# dio_adapter.net
KiCad netlist of a schematic drawn in EAGLE
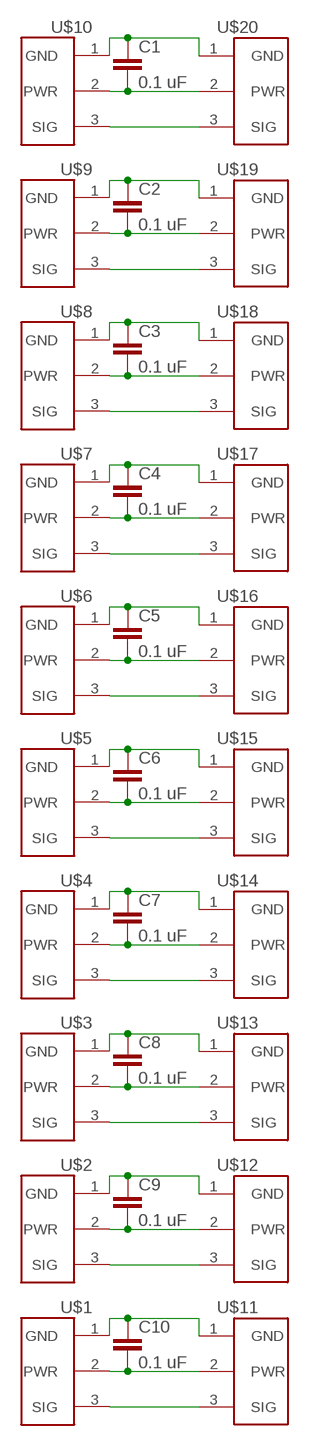
[diagram p0: schematic, sheet 1]

(export (version "E")
  (design (tool "Eeschema 10.0.6"))
  (components
    (comp (ref "C1")
      (value "0.1 uF")
      (footprint "eagle-import:0603")
      (libsource (lib "eagle-import") (part "CAP0603"))
    )
    (comp (ref "C2")
      (value "0.1 uF")
      (footprint "eagle-import:0603")
      (libsource (lib "eagle-import") (part "CAP0603"))
    )
    (comp (ref "C3")
      (value "0.1 uF")
      (footprint "eagle-import:0603")
      (libsource (lib "eagle-import") (part "CAP0603"))
    )
    (comp (ref "C4")
      (value "0.1 uF")
      (footprint "eagle-import:0603")
      (libsource (lib "eagle-import") (part "CAP0603"))
    )
    (comp (ref "C5")
      (value "0.1 uF")
      (footprint "eagle-import:0603")
      (libsource (lib "eagle-import") (part "CAP0603"))
    )
    (comp (ref "C6")
      (value "0.1 uF")
      (footprint "eagle-import:0603")
      (libsource (lib "eagle-import") (part "CAP0603"))
    )
    (comp (ref "C7")
      (value "0.1 uF")
      (footprint "eagle-import:0603")
      (libsource (lib "eagle-import") (part "CAP0603"))
    )
    (comp (ref "C8")
      (value "0.1 uF")
      (footprint "eagle-import:0603")
      (libsource (lib "eagle-import") (part "CAP0603"))
    )
    (comp (ref "C9")
      (value "0.1 uF")
      (footprint "eagle-import:0603")
      (libsource (lib "eagle-import") (part "CAP0603"))
    )
    (comp (ref "C10")
      (value "0.1 uF")
      (footprint "eagle-import:0603")
      (libsource (lib "eagle-import") (part "CAP0603"))
    )
    (comp (ref "U$1")
      (value "22-23-2031GENERIC")
      (footprint "eagle-import:PWM_1X3")
      (libsource (lib "eagle-import") (part "22-23-2031GENERIC"))
    )
    (comp (ref "U$2")
      (value "22-23-2031GENERIC")
      (footprint "eagle-import:PWM_1X3")
      (libsource (lib "eagle-import") (part "22-23-2031GENERIC"))
    )
    (comp (ref "U$3")
      (value "22-23-2031GENERIC")
      (footprint "eagle-import:PWM_1X3")
      (libsource (lib "eagle-import") (part "22-23-2031GENERIC"))
    )
    (comp (ref "U$4")
      (value "22-23-2031GENERIC")
      (footprint "eagle-import:PWM_1X3")
      (libsource (lib "eagle-import") (part "22-23-2031GENERIC"))
    )
    (comp (ref "U$5")
      (value "22-23-2031GENERIC")
      (footprint "eagle-import:PWM_1X3")
      (libsource (lib "eagle-import") (part "22-23-2031GENERIC"))
    )
    (comp (ref "U$6")
      (value "22-23-2031GENERIC")
      (footprint "eagle-import:PWM_1X3")
      (libsource (lib "eagle-import") (part "22-23-2031GENERIC"))
    )
    (comp (ref "U$7")
      (value "22-23-2031GENERIC")
      (footprint "eagle-import:PWM_1X3")
      (libsource (lib "eagle-import") (part "22-23-2031GENERIC"))
    )
    (comp (ref "U$8")
      (value "22-23-2031GENERIC")
      (footprint "eagle-import:PWM_1X3")
      (libsource (lib "eagle-import") (part "22-23-2031GENERIC"))
    )
    (comp (ref "U$9")
      (value "22-23-2031GENERIC")
      (footprint "eagle-import:PWM_1X3")
      (libsource (lib "eagle-import") (part "22-23-2031GENERIC"))
    )
    (comp (ref "U$10")
      (value "22-23-2031GENERIC")
      (footprint "eagle-import:PWM_1X3")
      (libsource (lib "eagle-import") (part "22-23-2031GENERIC"))
    )
    (comp (ref "U$11")
      (value "22-23-2031")
      (footprint "eagle-import:22-23-2031")
      (libsource (lib "eagle-import") (part "22-23-2031"))
    )
    (comp (ref "U$12")
      (value "22-23-2031")
      (footprint "eagle-import:22-23-2031")
      (libsource (lib "eagle-import") (part "22-23-2031"))
    )
    (comp (ref "U$13")
      (value "22-23-2031")
      (footprint "eagle-import:22-23-2031")
      (libsource (lib "eagle-import") (part "22-23-2031"))
    )
    (comp (ref "U$14")
      (value "22-23-2031")
      (footprint "eagle-import:22-23-2031")
      (libsource (lib "eagle-import") (part "22-23-2031"))
    )
    (comp (ref "U$15")
      (value "22-23-2031")
      (footprint "eagle-import:22-23-2031")
      (libsource (lib "eagle-import") (part "22-23-2031"))
    )
    (comp (ref "U$16")
      (value "22-23-2031")
      (footprint "eagle-import:22-23-2031")
      (libsource (lib "eagle-import") (part "22-23-2031"))
    )
    (comp (ref "U$17")
      (value "22-23-2031")
      (footprint "eagle-import:22-23-2031")
      (libsource (lib "eagle-import") (part "22-23-2031"))
    )
    (comp (ref "U$18")
      (value "22-23-2031")
      (footprint "eagle-import:22-23-2031")
      (libsource (lib "eagle-import") (part "22-23-2031"))
    )
    (comp (ref "U$19")
      (value "22-23-2031")
      (footprint "eagle-import:22-23-2031")
      (libsource (lib "eagle-import") (part "22-23-2031"))
    )
    (comp (ref "U$20")
      (value "22-23-2031")
      (footprint "eagle-import:22-23-2031")
      (libsource (lib "eagle-import") (part "22-23-2031"))
    )
  )
  (nets
    (net (code "1") (name "Net-(U$1-GND)") (class "Default")
      (node (ref "C10") (pin "1") (pinfunction "1_1") (pintype "passive"))
      (node (ref "U$1") (pin "1") (pinfunction "GND_1") (pintype "power_in"))
      (node (ref "U$11") (pin "1") (pinfunction "GND_1") (pintype "power_in"))
    )
    (net (code "2") (name "Net-(U$1-PWR)") (class "Default")
      (node (ref "C10") (pin "2") (pinfunction "2_2") (pintype "passive"))
      (node (ref "U$1") (pin "2") (pinfunction "PWR_2") (pintype "power_in"))
      (node (ref "U$11") (pin "2") (pinfunction "PWR_2") (pintype "power_in"))
    )
    (net (code "3") (name "Net-(U$1-SIG)") (class "Default")
      (node (ref "U$1") (pin "3") (pinfunction "SIG_3") (pintype "bidirectional"))
      (node (ref "U$11") (pin "3") (pinfunction "SIG_3") (pintype "bidirectional"))
    )
    (net (code "4") (name "Net-(U$10-GND)") (class "Default")
      (node (ref "C1") (pin "1") (pinfunction "1_1") (pintype "passive"))
      (node (ref "U$10") (pin "1") (pinfunction "GND_1") (pintype "power_in"))
      (node (ref "U$20") (pin "1") (pinfunction "GND_1") (pintype "power_in"))
    )
    (net (code "5") (name "Net-(U$10-PWR)") (class "Default")
      (node (ref "C1") (pin "2") (pinfunction "2_2") (pintype "passive"))
      (node (ref "U$10") (pin "2") (pinfunction "PWR_2") (pintype "power_in"))
      (node (ref "U$20") (pin "2") (pinfunction "PWR_2") (pintype "power_in"))
    )
    (net (code "6") (name "Net-(U$10-SIG)") (class "Default")
      (node (ref "U$10") (pin "3") (pinfunction "SIG_3") (pintype "bidirectional"))
      (node (ref "U$20") (pin "3") (pinfunction "SIG_3") (pintype "bidirectional"))
    )
    (net (code "7") (name "Net-(U$12-GND)") (class "Default")
      (node (ref "C9") (pin "1") (pinfunction "1_1") (pintype "passive"))
      (node (ref "U$12") (pin "1") (pinfunction "GND_1") (pintype "power_in"))
      (node (ref "U$2") (pin "1") (pinfunction "GND_1") (pintype "power_in"))
    )
    (net (code "8") (name "Net-(U$12-PWR)") (class "Default")
      (node (ref "C9") (pin "2") (pinfunction "2_2") (pintype "passive"))
      (node (ref "U$12") (pin "2") (pinfunction "PWR_2") (pintype "power_in"))
      (node (ref "U$2") (pin "2") (pinfunction "PWR_2") (pintype "power_in"))
    )
    (net (code "9") (name "Net-(U$12-SIG)") (class "Default")
      (node (ref "U$12") (pin "3") (pinfunction "SIG_3") (pintype "bidirectional"))
      (node (ref "U$2") (pin "3") (pinfunction "SIG_3") (pintype "bidirectional"))
    )
    (net (code "10") (name "Net-(U$13-GND)") (class "Default")
      (node (ref "C8") (pin "1") (pinfunction "1_1") (pintype "passive"))
      (node (ref "U$13") (pin "1") (pinfunction "GND_1") (pintype "power_in"))
      (node (ref "U$3") (pin "1") (pinfunction "GND_1") (pintype "power_in"))
    )
    (net (code "11") (name "Net-(U$13-PWR)") (class "Default")
      (node (ref "C8") (pin "2") (pinfunction "2_2") (pintype "passive"))
      (node (ref "U$13") (pin "2") (pinfunction "PWR_2") (pintype "power_in"))
      (node (ref "U$3") (pin "2") (pinfunction "PWR_2") (pintype "power_in"))
    )
    (net (code "12") (name "Net-(U$13-SIG)") (class "Default")
      (node (ref "U$13") (pin "3") (pinfunction "SIG_3") (pintype "bidirectional"))
      (node (ref "U$3") (pin "3") (pinfunction "SIG_3") (pintype "bidirectional"))
    )
    (net (code "13") (name "Net-(U$14-GND)") (class "Default")
      (node (ref "C7") (pin "1") (pinfunction "1_1") (pintype "passive"))
      (node (ref "U$14") (pin "1") (pinfunction "GND_1") (pintype "power_in"))
      (node (ref "U$4") (pin "1") (pinfunction "GND_1") (pintype "power_in"))
    )
    (net (code "14") (name "Net-(U$14-PWR)") (class "Default")
      (node (ref "C7") (pin "2") (pinfunction "2_2") (pintype "passive"))
      (node (ref "U$14") (pin "2") (pinfunction "PWR_2") (pintype "power_in"))
      (node (ref "U$4") (pin "2") (pinfunction "PWR_2") (pintype "power_in"))
    )
    (net (code "15") (name "Net-(U$14-SIG)") (class "Default")
      (node (ref "U$14") (pin "3") (pinfunction "SIG_3") (pintype "bidirectional"))
      (node (ref "U$4") (pin "3") (pinfunction "SIG_3") (pintype "bidirectional"))
    )
    (net (code "16") (name "Net-(U$15-GND)") (class "Default")
      (node (ref "C6") (pin "1") (pinfunction "1_1") (pintype "passive"))
      (node (ref "U$15") (pin "1") (pinfunction "GND_1") (pintype "power_in"))
      (node (ref "U$5") (pin "1") (pinfunction "GND_1") (pintype "power_in"))
    )
    (net (code "17") (name "Net-(U$15-PWR)") (class "Default")
      (node (ref "C6") (pin "2") (pinfunction "2_2") (pintype "passive"))
      (node (ref "U$15") (pin "2") (pinfunction "PWR_2") (pintype "power_in"))
      (node (ref "U$5") (pin "2") (pinfunction "PWR_2") (pintype "power_in"))
    )
    (net (code "18") (name "Net-(U$15-SIG)") (class "Default")
      (node (ref "U$15") (pin "3") (pinfunction "SIG_3") (pintype "bidirectional"))
      (node (ref "U$5") (pin "3") (pinfunction "SIG_3") (pintype "bidirectional"))
    )
    (net (code "19") (name "Net-(U$16-GND)") (class "Default")
      (node (ref "C5") (pin "1") (pinfunction "1_1") (pintype "passive"))
      (node (ref "U$16") (pin "1") (pinfunction "GND_1") (pintype "power_in"))
      (node (ref "U$6") (pin "1") (pinfunction "GND_1") (pintype "power_in"))
    )
    (net (code "20") (name "Net-(U$16-PWR)") (class "Default")
      (node (ref "C5") (pin "2") (pinfunction "2_2") (pintype "passive"))
      (node (ref "U$16") (pin "2") (pinfunction "PWR_2") (pintype "power_in"))
      (node (ref "U$6") (pin "2") (pinfunction "PWR_2") (pintype "power_in"))
    )
    (net (code "21") (name "Net-(U$16-SIG)") (class "Default")
      (node (ref "U$16") (pin "3") (pinfunction "SIG_3") (pintype "bidirectional"))
      (node (ref "U$6") (pin "3") (pinfunction "SIG_3") (pintype "bidirectional"))
    )
    (net (code "22") (name "Net-(U$17-GND)") (class "Default")
      (node (ref "C4") (pin "1") (pinfunction "1_1") (pintype "passive"))
      (node (ref "U$17") (pin "1") (pinfunction "GND_1") (pintype "power_in"))
      (node (ref "U$7") (pin "1") (pinfunction "GND_1") (pintype "power_in"))
    )
    (net (code "23") (name "Net-(U$17-PWR)") (class "Default")
      (node (ref "C4") (pin "2") (pinfunction "2_2") (pintype "passive"))
      (node (ref "U$17") (pin "2") (pinfunction "PWR_2") (pintype "power_in"))
      (node (ref "U$7") (pin "2") (pinfunction "PWR_2") (pintype "power_in"))
    )
    (net (code "24") (name "Net-(U$17-SIG)") (class "Default")
      (node (ref "U$17") (pin "3") (pinfunction "SIG_3") (pintype "bidirectional"))
      (node (ref "U$7") (pin "3") (pinfunction "SIG_3") (pintype "bidirectional"))
    )
    (net (code "25") (name "Net-(U$18-GND)") (class "Default")
      (node (ref "C3") (pin "1") (pinfunction "1_1") (pintype "passive"))
      (node (ref "U$18") (pin "1") (pinfunction "GND_1") (pintype "power_in"))
      (node (ref "U$8") (pin "1") (pinfunction "GND_1") (pintype "power_in"))
    )
    (net (code "26") (name "Net-(U$18-PWR)") (class "Default")
      (node (ref "C3") (pin "2") (pinfunction "2_2") (pintype "passive"))
      (node (ref "U$18") (pin "2") (pinfunction "PWR_2") (pintype "power_in"))
      (node (ref "U$8") (pin "2") (pinfunction "PWR_2") (pintype "power_in"))
    )
    (net (code "27") (name "Net-(U$18-SIG)") (class "Default")
      (node (ref "U$18") (pin "3") (pinfunction "SIG_3") (pintype "bidirectional"))
      (node (ref "U$8") (pin "3") (pinfunction "SIG_3") (pintype "bidirectional"))
    )
    (net (code "28") (name "Net-(U$19-GND)") (class "Default")
      (node (ref "C2") (pin "1") (pinfunction "1_1") (pintype "passive"))
      (node (ref "U$19") (pin "1") (pinfunction "GND_1") (pintype "power_in"))
      (node (ref "U$9") (pin "1") (pinfunction "GND_1") (pintype "power_in"))
    )
    (net (code "29") (name "Net-(U$19-PWR)") (class "Default")
      (node (ref "C2") (pin "2") (pinfunction "2_2") (pintype "passive"))
      (node (ref "U$19") (pin "2") (pinfunction "PWR_2") (pintype "power_in"))
      (node (ref "U$9") (pin "2") (pinfunction "PWR_2") (pintype "power_in"))
    )
    (net (code "30") (name "Net-(U$19-SIG)") (class "Default")
      (node (ref "U$19") (pin "3") (pinfunction "SIG_3") (pintype "bidirectional"))
      (node (ref "U$9") (pin "3") (pinfunction "SIG_3") (pintype "bidirectional"))
    )
  )
)
